# SP8T_ecal_2.net
KiCad netlist of a schematic drawn in Altium Designer
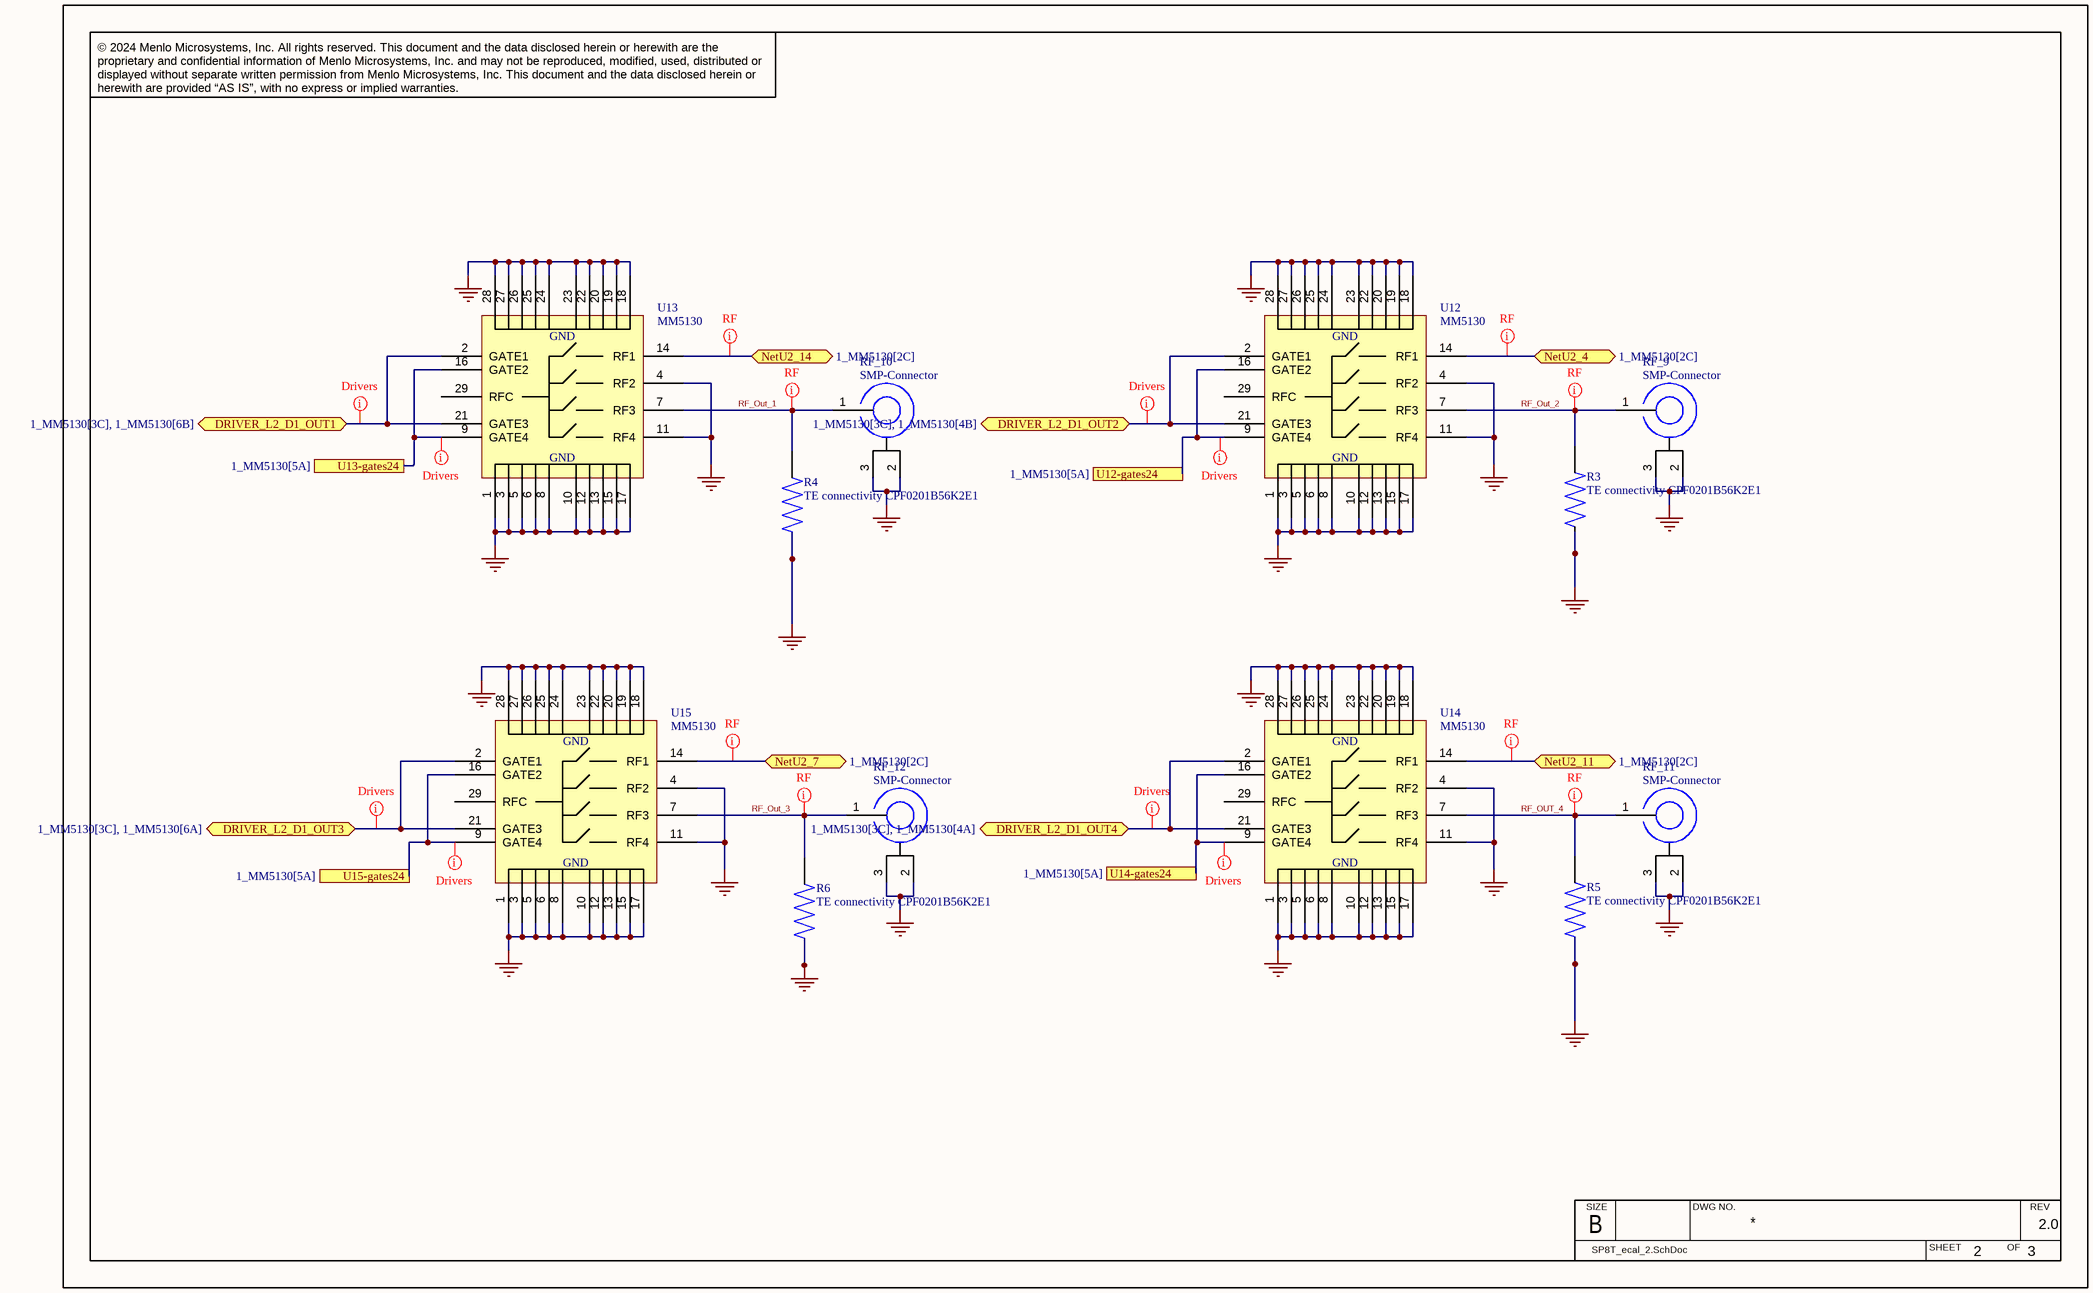
[diagram p0: SP8T_ecal_2.SchDoc]

(export (version "E")
  (design (tool "Eeschema 10.0.6"))
  (components
    (comp (ref "R3")
      (value "TE connectivity CPF0201B56K2E1")
      (footprint "0201-resistor")
      (description "CPF 0201 56K2 0.1% 25PPM 1K RL")
      (fields (field (name "MP") "ERJ1GN0R00C") (field (name "MFGR PART NO.") "CPF0201B56K2E1"))
      (libsource (lib "SchlibLafe") (part "TE connectivity CPF0201B56K2E1"))
    )
    (comp (ref "R4")
      (value "TE connectivity CPF0201B56K2E1")
      (footprint "0201-resistor")
      (description "CPF 0201 56K2 0.1% 25PPM 1K RL")
      (fields (field (name "MP") "ERJ1GN0R00C") (field (name "MFGR PART NO.") "CPF0201B56K2E1"))
      (libsource (lib "SchlibLafe") (part "TE connectivity CPF0201B56K2E1"))
    )
    (comp (ref "R5")
      (value "TE connectivity CPF0201B56K2E1")
      (footprint "0201-resistor")
      (description "CPF 0201 56K2 0.1% 25PPM 1K RL")
      (fields (field (name "MP") "ERJ1GN0R00C") (field (name "MFGR PART NO.") "CPF0201B56K2E1"))
      (libsource (lib "SchlibLafe") (part "TE connectivity CPF0201B56K2E1"))
    )
    (comp (ref "R6")
      (value "TE connectivity CPF0201B56K2E1")
      (footprint "0201-resistor")
      (description "CPF 0201 56K2 0.1% 25PPM 1K RL")
      (fields (field (name "MP") "ERJ1GN0R00C") (field (name "MFGR PART NO.") "CPF0201B56K2E1"))
      (libsource (lib "SchlibLafe") (part "TE connectivity CPF0201B56K2E1"))
    )
    (comp (ref "RF_9")
      (value "PE44490")
      (footprint "CONN-PE44490")
      (description "SMP, Mini Connector Plug, Male Pin 50 Ohms Board Edge, Cutout; Surface Mount Solder")
      (fields (field (name "MANUFACTURER") "Pasternack") (field (name "TYPE") "SMP-Connector"))
      (libsource (lib "Menlo_Altium_Library") (part "CONN-PE44490"))
    )
    (comp (ref "RF_10")
      (value "PE44490")
      (footprint "CONN-PE44490")
      (description "SMP, Mini Connector Plug, Male Pin 50 Ohms Board Edge, Cutout; Surface Mount Solder")
      (fields (field (name "MANUFACTURER") "Pasternack") (field (name "TYPE") "SMP-Connector"))
      (libsource (lib "Menlo_Altium_Library") (part "CONN-PE44490"))
    )
    (comp (ref "RF_11")
      (value "PE44490")
      (footprint "CONN-PE44490")
      (description "SMP, Mini Connector Plug, Male Pin 50 Ohms Board Edge, Cutout; Surface Mount Solder")
      (fields (field (name "MANUFACTURER") "Pasternack") (field (name "TYPE") "SMP-Connector"))
      (libsource (lib "Menlo_Altium_Library") (part "CONN-PE44490"))
    )
    (comp (ref "RF_12")
      (value "PE44490")
      (footprint "CONN-PE44490")
      (description "SMP, Mini Connector Plug, Male Pin 50 Ohms Board Edge, Cutout; Surface Mount Solder")
      (fields (field (name "MANUFACTURER") "Pasternack") (field (name "TYPE") "SMP-Connector"))
      (libsource (lib "Menlo_Altium_Library") (part "CONN-PE44490"))
    )
    (comp (ref "U12")
      (value "MM5130")
      (footprint "MM5130-SP_M_PCB_NOFLOOD")
      (description "High power SP4T MEMs switch")
      (libsource (lib "Menlo_Altium_Library") (part "IC-MM5130"))
    )
    (comp (ref "U13")
      (value "MM5130")
      (footprint "MM5130-SP_M_PCB_NOFLOOD")
      (description "High power SP4T MEMs switch")
      (libsource (lib "Menlo_Altium_Library") (part "IC-MM5130"))
    )
    (comp (ref "U14")
      (value "MM5130")
      (footprint "MM5130-SP_M_PCB_NOFLOOD")
      (description "High power SP4T MEMs switch")
      (libsource (lib "Menlo_Altium_Library") (part "IC-MM5130"))
    )
    (comp (ref "U15")
      (value "MM5130")
      (footprint "MM5130-SP_M_PCB_NOFLOOD")
      (description "High power SP4T MEMs switch")
      (libsource (lib "Menlo_Altium_Library") (part "IC-MM5130"))
    )
  )
  (nets
    (net (code "1") (name "/DRIVER_L2_D1_OUT1") (class "Default")
      (node (ref "U13") (pin "2") (pinfunction "GATE1_2") (pintype "passive"))
      (node (ref "U13") (pin "21") (pinfunction "GATE3_21") (pintype "passive"))
    )
    (net (code "2") (name "/DRIVER_L2_D1_OUT2") (class "Default")
      (node (ref "U12") (pin "2") (pinfunction "GATE1_2") (pintype "passive"))
      (node (ref "U12") (pin "21") (pinfunction "GATE3_21") (pintype "passive"))
    )
    (net (code "3") (name "/DRIVER_L2_D1_OUT3") (class "Default")
      (node (ref "U15") (pin "2") (pinfunction "GATE1_2") (pintype "passive"))
      (node (ref "U15") (pin "21") (pinfunction "GATE3_21") (pintype "passive"))
    )
    (net (code "4") (name "/DRIVER_L2_D1_OUT4") (class "Default")
      (node (ref "U14") (pin "2") (pinfunction "GATE1_2") (pintype "passive"))
      (node (ref "U14") (pin "21") (pinfunction "GATE3_21") (pintype "passive"))
    )
    (net (code "5") (name "/NetU2_4") (class "Default")
      (node (ref "U12") (pin "14") (pinfunction "RF1_14") (pintype "passive"))
    )
    (net (code "6") (name "/NetU2_7") (class "Default")
      (node (ref "U15") (pin "14") (pinfunction "RF1_14") (pintype "passive"))
    )
    (net (code "7") (name "/NetU2_11") (class "Default")
      (node (ref "U14") (pin "14") (pinfunction "RF1_14") (pintype "passive"))
    )
    (net (code "8") (name "/NetU2_14") (class "Default")
      (node (ref "U13") (pin "14") (pinfunction "RF1_14") (pintype "passive"))
    )
    (net (code "9") (name "/RF_OUT_4") (class "Default")
      (node (ref "R5") (pin "1") (pinfunction "1_1") (pintype "passive"))
      (node (ref "RF_11") (pin "1") (pinfunction "1_1") (pintype "passive"))
      (node (ref "U14") (pin "7") (pinfunction "RF3_7") (pintype "passive"))
    )
    (net (code "10") (name "/RF_Out_1") (class "Default")
      (node (ref "R4") (pin "1") (pinfunction "1_1") (pintype "passive"))
      (node (ref "RF_10") (pin "1") (pinfunction "1_1") (pintype "passive"))
      (node (ref "U13") (pin "7") (pinfunction "RF3_7") (pintype "passive"))
    )
    (net (code "11") (name "/RF_Out_2") (class "Default")
      (node (ref "R3") (pin "1") (pinfunction "1_1") (pintype "passive"))
      (node (ref "RF_9") (pin "1") (pinfunction "1_1") (pintype "passive"))
      (node (ref "U12") (pin "7") (pinfunction "RF3_7") (pintype "passive"))
    )
    (net (code "12") (name "/RF_Out_3") (class "Default")
      (node (ref "R6") (pin "1") (pinfunction "1_1") (pintype "passive"))
      (node (ref "RF_12") (pin "1") (pinfunction "1_1") (pintype "passive"))
      (node (ref "U15") (pin "7") (pinfunction "RF3_7") (pintype "passive"))
    )
    (net (code "13") (name "/U12-gates24") (class "Default")
      (node (ref "U12") (pin "16") (pinfunction "GATE2_16") (pintype "passive"))
      (node (ref "U12") (pin "9") (pinfunction "GATE4_9") (pintype "passive"))
    )
    (net (code "14") (name "/U13-gates24") (class "Default")
      (node (ref "U13") (pin "16") (pinfunction "GATE2_16") (pintype "passive"))
      (node (ref "U13") (pin "9") (pinfunction "GATE4_9") (pintype "passive"))
    )
    (net (code "15") (name "/U14-gates24") (class "Default")
      (node (ref "U14") (pin "16") (pinfunction "GATE2_16") (pintype "passive"))
      (node (ref "U14") (pin "9") (pinfunction "GATE4_9") (pintype "passive"))
    )
    (net (code "16") (name "/U15-gates24") (class "Default")
      (node (ref "U15") (pin "16") (pinfunction "GATE2_16") (pintype "passive"))
      (node (ref "U15") (pin "9") (pinfunction "GATE4_9") (pintype "passive"))
    )
    (net (code "17") (name "GND") (class "Default")
      (node (ref "R3") (pin "2") (pinfunction "2_2") (pintype "passive"))
      (node (ref "R4") (pin "2") (pinfunction "2_2") (pintype "passive"))
      (node (ref "R5") (pin "2") (pinfunction "2_2") (pintype "passive"))
      (node (ref "R6") (pin "2") (pinfunction "2_2") (pintype "passive"))
      (node (ref "RF_10") (pin "2") (pinfunction "2_2") (pintype "passive"))
      (node (ref "RF_10") (pin "3") (pinfunction "3_3") (pintype "passive"))
      (node (ref "RF_11") (pin "2") (pinfunction "2_2") (pintype "passive"))
      (node (ref "RF_11") (pin "3") (pinfunction "3_3") (pintype "passive"))
      (node (ref "RF_12") (pin "2") (pinfunction "2_2") (pintype "passive"))
      (node (ref "RF_12") (pin "3") (pinfunction "3_3") (pintype "passive"))
      (node (ref "RF_9") (pin "2") (pinfunction "2_2") (pintype "passive"))
      (node (ref "RF_9") (pin "3") (pinfunction "3_3") (pintype "passive"))
      (node (ref "U12") (pin "1") (pinfunction "GND_1") (pintype "passive"))
      (node (ref "U12") (pin "10") (pinfunction "GND_10") (pintype "passive"))
      (node (ref "U12") (pin "11") (pinfunction "RF4_11") (pintype "passive"))
      (node (ref "U12") (pin "12") (pinfunction "GND_12") (pintype "passive"))
      (node (ref "U12") (pin "13") (pinfunction "GND_13") (pintype "passive"))
      (node (ref "U12") (pin "15") (pinfunction "GND_15") (pintype "passive"))
      (node (ref "U12") (pin "17") (pinfunction "GND_17") (pintype "passive"))
      (node (ref "U12") (pin "18") (pinfunction "GND_18") (pintype "passive"))
      (node (ref "U12") (pin "19") (pinfunction "GND_19") (pintype "passive"))
      (node (ref "U12") (pin "20") (pinfunction "GND_20") (pintype "passive"))
      (node (ref "U12") (pin "22") (pinfunction "GND_22") (pintype "passive"))
      (node (ref "U12") (pin "23") (pinfunction "GND_23") (pintype "passive"))
      (node (ref "U12") (pin "24") (pinfunction "GND_24") (pintype "passive"))
      (node (ref "U12") (pin "25") (pinfunction "GND_25") (pintype "passive"))
      (node (ref "U12") (pin "26") (pinfunction "GND_26") (pintype "passive"))
      (node (ref "U12") (pin "27") (pinfunction "GND_27") (pintype "passive"))
      (node (ref "U12") (pin "28") (pinfunction "GND_28") (pintype "passive"))
      (node (ref "U12") (pin "3") (pinfunction "GND_3") (pintype "passive"))
      (node (ref "U12") (pin "4") (pinfunction "RF2_4") (pintype "passive"))
      (node (ref "U12") (pin "5") (pinfunction "GND_5") (pintype "passive"))
      (node (ref "U12") (pin "6") (pinfunction "GND_6") (pintype "passive"))
      (node (ref "U12") (pin "8") (pinfunction "GND_8") (pintype "passive"))
      (node (ref "U13") (pin "1") (pinfunction "GND_1") (pintype "passive"))
      (node (ref "U13") (pin "10") (pinfunction "GND_10") (pintype "passive"))
      (node (ref "U13") (pin "11") (pinfunction "RF4_11") (pintype "passive"))
      (node (ref "U13") (pin "12") (pinfunction "GND_12") (pintype "passive"))
      (node (ref "U13") (pin "13") (pinfunction "GND_13") (pintype "passive"))
      (node (ref "U13") (pin "15") (pinfunction "GND_15") (pintype "passive"))
      (node (ref "U13") (pin "17") (pinfunction "GND_17") (pintype "passive"))
      (node (ref "U13") (pin "18") (pinfunction "GND_18") (pintype "passive"))
      (node (ref "U13") (pin "19") (pinfunction "GND_19") (pintype "passive"))
      (node (ref "U13") (pin "20") (pinfunction "GND_20") (pintype "passive"))
      (node (ref "U13") (pin "22") (pinfunction "GND_22") (pintype "passive"))
      (node (ref "U13") (pin "23") (pinfunction "GND_23") (pintype "passive"))
      (node (ref "U13") (pin "24") (pinfunction "GND_24") (pintype "passive"))
      (node (ref "U13") (pin "25") (pinfunction "GND_25") (pintype "passive"))
      (node (ref "U13") (pin "26") (pinfunction "GND_26") (pintype "passive"))
      (node (ref "U13") (pin "27") (pinfunction "GND_27") (pintype "passive"))
      (node (ref "U13") (pin "28") (pinfunction "GND_28") (pintype "passive"))
      (node (ref "U13") (pin "3") (pinfunction "GND_3") (pintype "passive"))
      (node (ref "U13") (pin "4") (pinfunction "RF2_4") (pintype "passive"))
      (node (ref "U13") (pin "5") (pinfunction "GND_5") (pintype "passive"))
      (node (ref "U13") (pin "6") (pinfunction "GND_6") (pintype "passive"))
      (node (ref "U13") (pin "8") (pinfunction "GND_8") (pintype "passive"))
      (node (ref "U14") (pin "1") (pinfunction "GND_1") (pintype "passive"))
      (node (ref "U14") (pin "10") (pinfunction "GND_10") (pintype "passive"))
      (node (ref "U14") (pin "11") (pinfunction "RF4_11") (pintype "passive"))
      (node (ref "U14") (pin "12") (pinfunction "GND_12") (pintype "passive"))
      (node (ref "U14") (pin "13") (pinfunction "GND_13") (pintype "passive"))
      (node (ref "U14") (pin "15") (pinfunction "GND_15") (pintype "passive"))
      (node (ref "U14") (pin "17") (pinfunction "GND_17") (pintype "passive"))
      (node (ref "U14") (pin "18") (pinfunction "GND_18") (pintype "passive"))
      (node (ref "U14") (pin "19") (pinfunction "GND_19") (pintype "passive"))
      (node (ref "U14") (pin "20") (pinfunction "GND_20") (pintype "passive"))
      (node (ref "U14") (pin "22") (pinfunction "GND_22") (pintype "passive"))
      (node (ref "U14") (pin "23") (pinfunction "GND_23") (pintype "passive"))
      (node (ref "U14") (pin "24") (pinfunction "GND_24") (pintype "passive"))
      (node (ref "U14") (pin "25") (pinfunction "GND_25") (pintype "passive"))
      (node (ref "U14") (pin "26") (pinfunction "GND_26") (pintype "passive"))
      (node (ref "U14") (pin "27") (pinfunction "GND_27") (pintype "passive"))
      (node (ref "U14") (pin "28") (pinfunction "GND_28") (pintype "passive"))
      (node (ref "U14") (pin "3") (pinfunction "GND_3") (pintype "passive"))
      (node (ref "U14") (pin "4") (pinfunction "RF2_4") (pintype "passive"))
      (node (ref "U14") (pin "5") (pinfunction "GND_5") (pintype "passive"))
      (node (ref "U14") (pin "6") (pinfunction "GND_6") (pintype "passive"))
      (node (ref "U14") (pin "8") (pinfunction "GND_8") (pintype "passive"))
      (node (ref "U15") (pin "1") (pinfunction "GND_1") (pintype "passive"))
      (node (ref "U15") (pin "10") (pinfunction "GND_10") (pintype "passive"))
      (node (ref "U15") (pin "11") (pinfunction "RF4_11") (pintype "passive"))
      (node (ref "U15") (pin "12") (pinfunction "GND_12") (pintype "passive"))
      (node (ref "U15") (pin "13") (pinfunction "GND_13") (pintype "passive"))
      (node (ref "U15") (pin "15") (pinfunction "GND_15") (pintype "passive"))
      (node (ref "U15") (pin "17") (pinfunction "GND_17") (pintype "passive"))
      (node (ref "U15") (pin "18") (pinfunction "GND_18") (pintype "passive"))
      (node (ref "U15") (pin "19") (pinfunction "GND_19") (pintype "passive"))
      (node (ref "U15") (pin "20") (pinfunction "GND_20") (pintype "passive"))
      (node (ref "U15") (pin "22") (pinfunction "GND_22") (pintype "passive"))
      (node (ref "U15") (pin "23") (pinfunction "GND_23") (pintype "passive"))
      (node (ref "U15") (pin "24") (pinfunction "GND_24") (pintype "passive"))
      (node (ref "U15") (pin "25") (pinfunction "GND_25") (pintype "passive"))
      (node (ref "U15") (pin "26") (pinfunction "GND_26") (pintype "passive"))
      (node (ref "U15") (pin "27") (pinfunction "GND_27") (pintype "passive"))
      (node (ref "U15") (pin "28") (pinfunction "GND_28") (pintype "passive"))
      (node (ref "U15") (pin "3") (pinfunction "GND_3") (pintype "passive"))
      (node (ref "U15") (pin "4") (pinfunction "RF2_4") (pintype "passive"))
      (node (ref "U15") (pin "5") (pinfunction "GND_5") (pintype "passive"))
      (node (ref "U15") (pin "6") (pinfunction "GND_6") (pintype "passive"))
      (node (ref "U15") (pin "8") (pinfunction "GND_8") (pintype "passive"))
    )
    (net (code "18") (name "unconnected-(U12-RFC-Pad29)") (class "Default")
      (node (ref "U12") (pin "29") (pinfunction "RFC_29") (pintype "passive"))
    )
    (net (code "19") (name "unconnected-(U13-RFC-Pad29)") (class "Default")
      (node (ref "U13") (pin "29") (pinfunction "RFC_29") (pintype "passive"))
    )
    (net (code "20") (name "unconnected-(U14-RFC-Pad29)") (class "Default")
      (node (ref "U14") (pin "29") (pinfunction "RFC_29") (pintype "passive"))
    )
    (net (code "21") (name "unconnected-(U15-RFC-Pad29)") (class "Default")
      (node (ref "U15") (pin "29") (pinfunction "RFC_29") (pintype "passive"))
    )
  )
)
